# FlexLight.net
KiCad netlist of a schematic drawn in EasyEDA
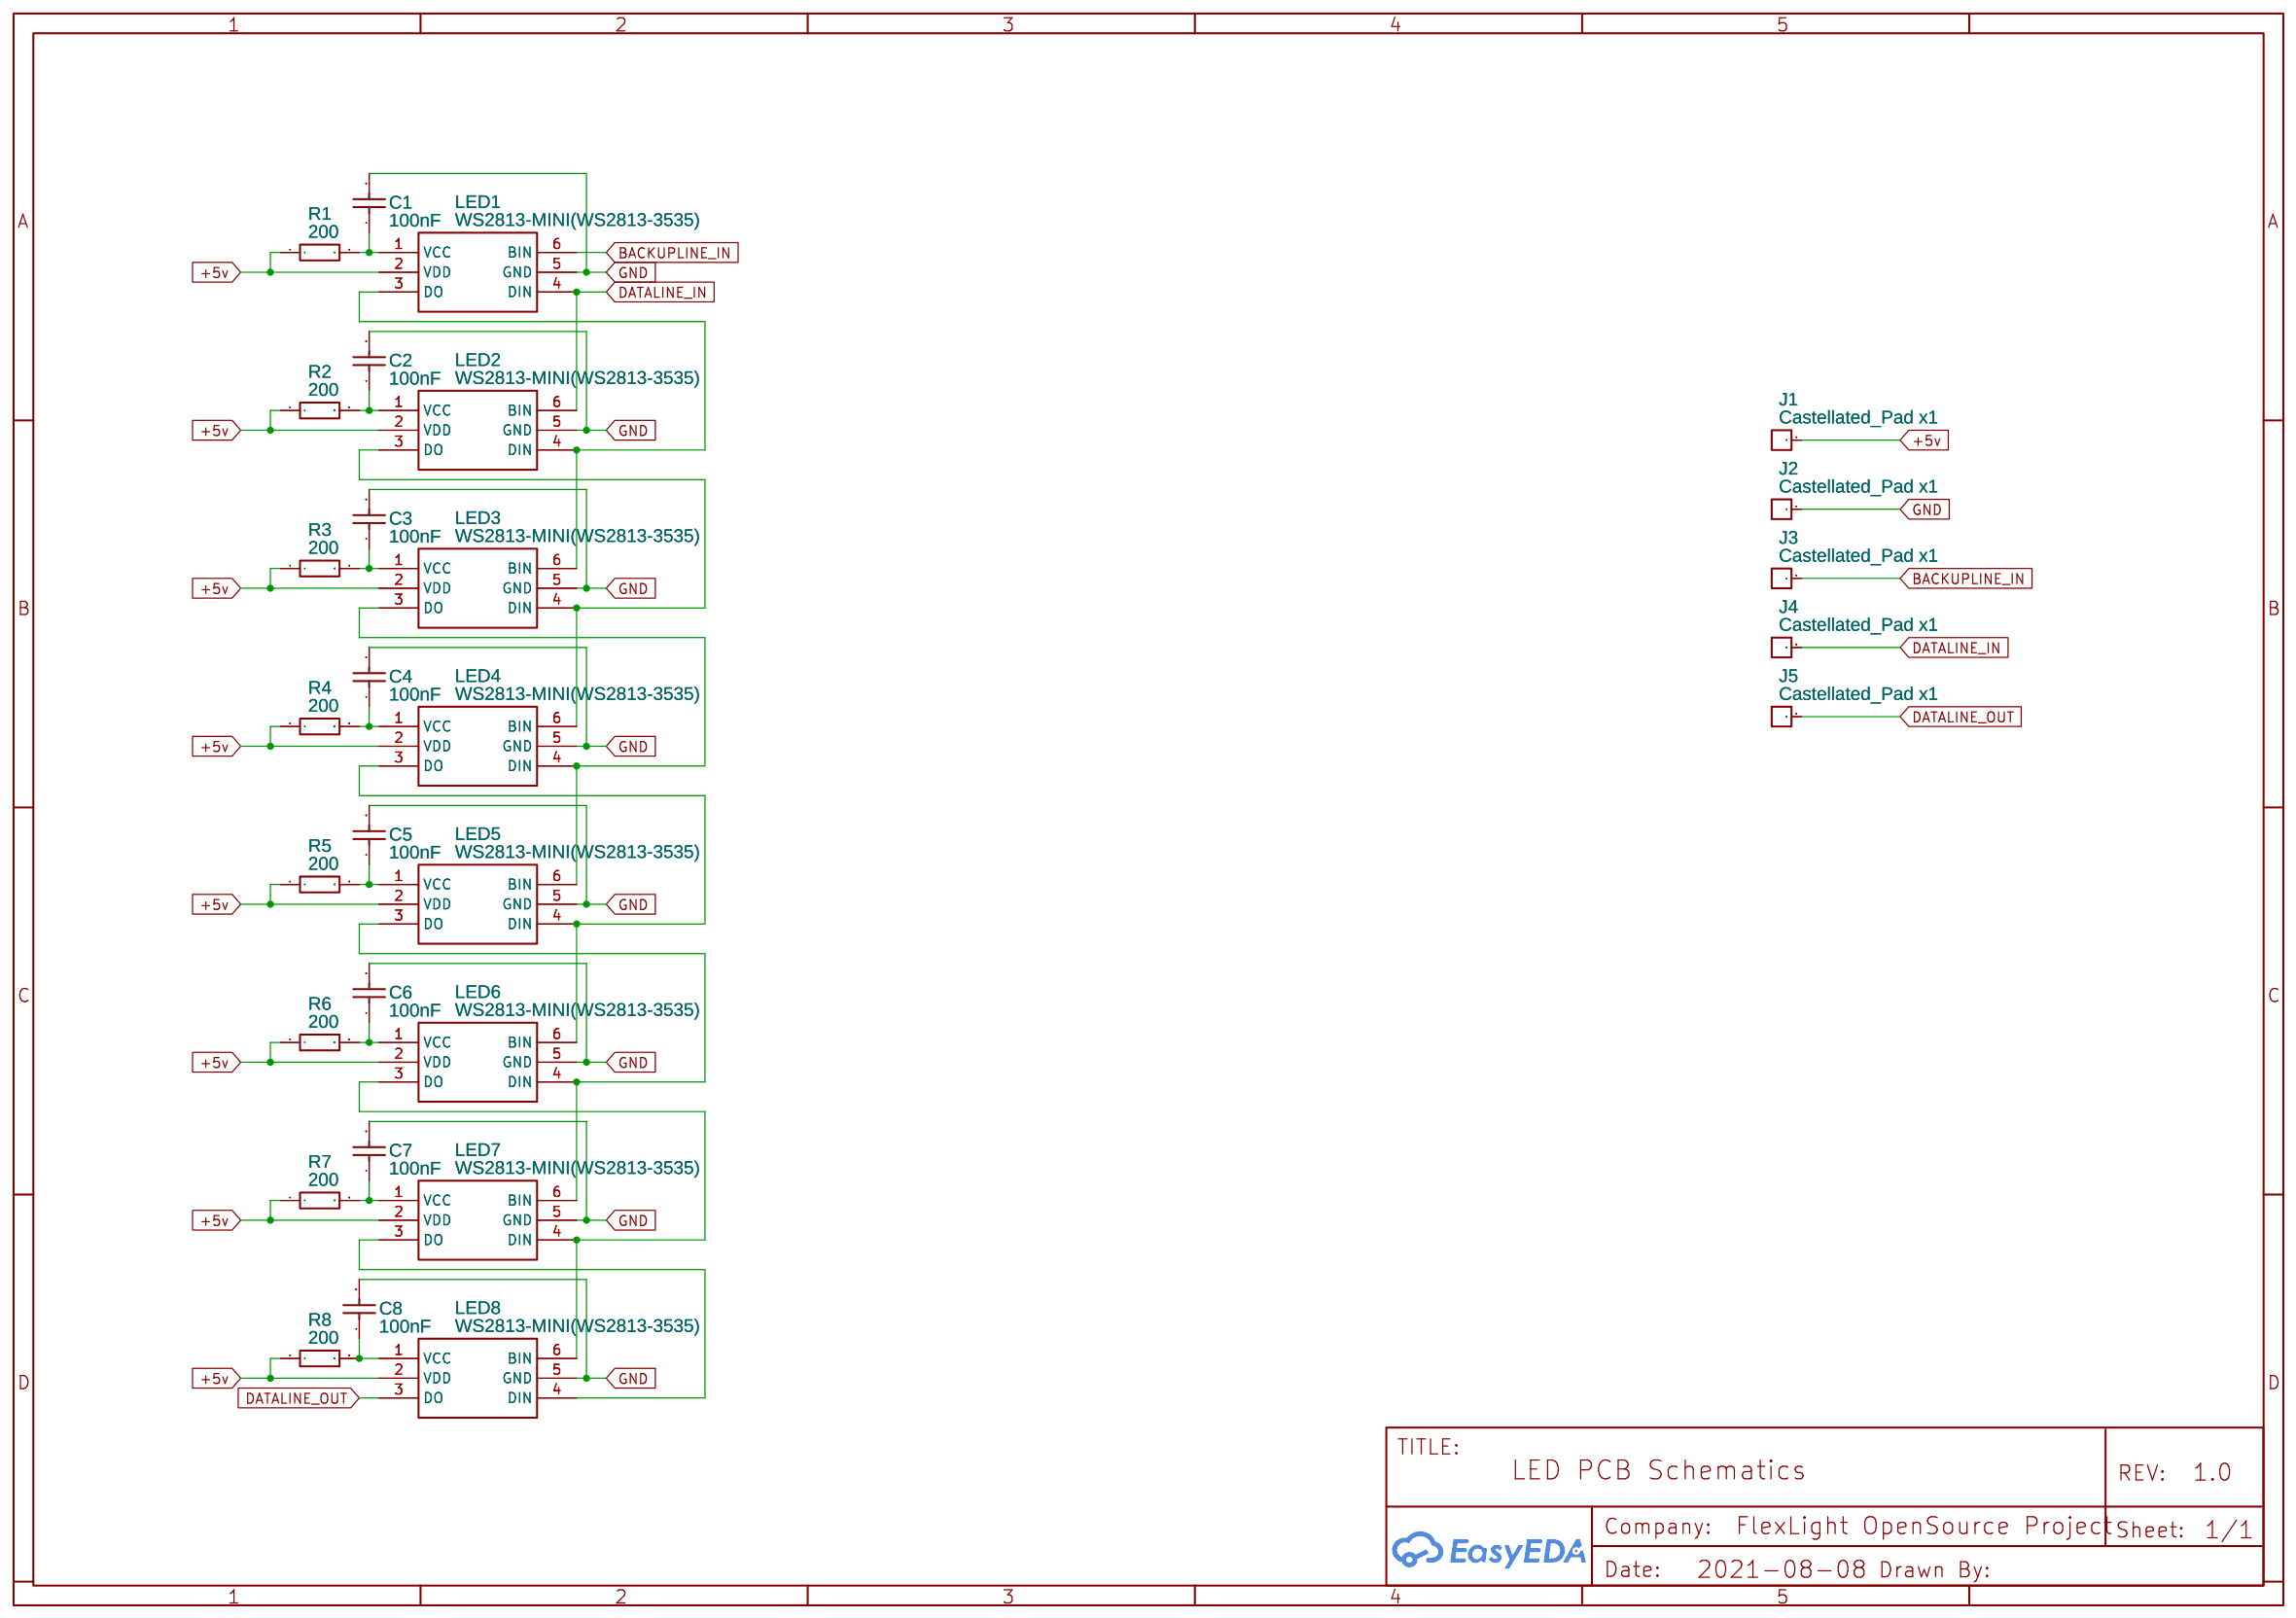
[diagram p0: schematic sheet]

(export (version "E")
  (design (tool "Eeschema 10.0.6"))
  (components
    (comp (ref "C1")
      (value "100nF")
      (fields
        (field (name "BOM_Manufacturer Part") "CL05B104KO5NNNC")
        (field (name "BOM_Supplier Part") "C1525")
      )
      (libsource (lib "") (part "CL05B104KO5NNNC"))
    )
    (comp (ref "C2")
      (value "100nF")
      (fields
        (field (name "BOM_Manufacturer Part") "CL05B104KO5NNNC")
        (field (name "BOM_Supplier Part") "C1525")
      )
      (libsource (lib "") (part "CL05B104KO5NNNC"))
    )
    (comp (ref "C3")
      (value "100nF")
      (fields
        (field (name "BOM_Manufacturer Part") "CL05B104KO5NNNC")
        (field (name "BOM_Supplier Part") "C1525")
      )
      (libsource (lib "") (part "CL05B104KO5NNNC"))
    )
    (comp (ref "C4")
      (value "100nF")
      (fields
        (field (name "BOM_Manufacturer Part") "CL05B104KO5NNNC")
        (field (name "BOM_Supplier Part") "C1525")
      )
      (libsource (lib "") (part "CL05B104KO5NNNC"))
    )
    (comp (ref "C5")
      (value "100nF")
      (fields
        (field (name "BOM_Manufacturer Part") "CL05B104KO5NNNC")
        (field (name "BOM_Supplier Part") "C1525")
      )
      (libsource (lib "") (part "CL05B104KO5NNNC"))
    )
    (comp (ref "C6")
      (value "100nF")
      (fields
        (field (name "BOM_Manufacturer Part") "CL05B104KO5NNNC")
        (field (name "BOM_Supplier Part") "C1525")
      )
      (libsource (lib "") (part "CL05B104KO5NNNC"))
    )
    (comp (ref "C7")
      (value "100nF")
      (fields
        (field (name "BOM_Manufacturer Part") "CL05B104KO5NNNC")
        (field (name "BOM_Supplier Part") "C1525")
      )
      (libsource (lib "") (part "CL05B104KO5NNNC"))
    )
    (comp (ref "C8")
      (value "100nF")
      (fields
        (field (name "BOM_Manufacturer Part") "CL05B104KO5NNNC")
        (field (name "BOM_Supplier Part") "C1525")
      )
      (libsource (lib "") (part "CL05B104KO5NNNC"))
    )
    (comp (ref "J1") (value "Castellated_Pad x1") (libsource (lib "") (part "Castellated_Pad x1")))
    (comp (ref "J2") (value "Castellated_Pad x1") (libsource (lib "") (part "Castellated_Pad x1")))
    (comp (ref "J3") (value "Castellated_Pad x1") (libsource (lib "") (part "Castellated_Pad x1")))
    (comp (ref "J4") (value "Castellated_Pad x1") (libsource (lib "") (part "Castellated_Pad x1")))
    (comp (ref "J5") (value "Castellated_Pad x1") (libsource (lib "") (part "Castellated_Pad x1")))
    (comp (ref "LED1")
      (value "WS2813-MINI(WS2813-3535)")
      (fields
        (field (name "BOM_Manufacturer Part") "WS2813-Mini(WS2813-3535)")
        (field (name "BOM_Supplier Part") "C189639")
      )
      (libsource (lib "") (part "WS2813-MINI(WS2813-3535)"))
    )
    (comp (ref "LED2")
      (value "WS2813-MINI(WS2813-3535)")
      (fields
        (field (name "BOM_Manufacturer Part") "WS2813-Mini(WS2813-3535)")
        (field (name "BOM_Supplier Part") "C189639")
      )
      (libsource (lib "") (part "WS2813-MINI(WS2813-3535)"))
    )
    (comp (ref "LED3")
      (value "WS2813-MINI(WS2813-3535)")
      (fields
        (field (name "BOM_Manufacturer Part") "WS2813-Mini(WS2813-3535)")
        (field (name "BOM_Supplier Part") "C189639")
      )
      (libsource (lib "") (part "WS2813-MINI(WS2813-3535)"))
    )
    (comp (ref "LED4")
      (value "WS2813-MINI(WS2813-3535)")
      (fields
        (field (name "BOM_Manufacturer Part") "WS2813-Mini(WS2813-3535)")
        (field (name "BOM_Supplier Part") "C189639")
      )
      (libsource (lib "") (part "WS2813-MINI(WS2813-3535)"))
    )
    (comp (ref "LED5")
      (value "WS2813-MINI(WS2813-3535)")
      (fields
        (field (name "BOM_Manufacturer Part") "WS2813-Mini(WS2813-3535)")
        (field (name "BOM_Supplier Part") "C189639")
      )
      (libsource (lib "") (part "WS2813-MINI(WS2813-3535)"))
    )
    (comp (ref "LED6")
      (value "WS2813-MINI(WS2813-3535)")
      (fields
        (field (name "BOM_Manufacturer Part") "WS2813-Mini(WS2813-3535)")
        (field (name "BOM_Supplier Part") "C189639")
      )
      (libsource (lib "") (part "WS2813-MINI(WS2813-3535)"))
    )
    (comp (ref "LED7")
      (value "WS2813-MINI(WS2813-3535)")
      (fields
        (field (name "BOM_Manufacturer Part") "WS2813-Mini(WS2813-3535)")
        (field (name "BOM_Supplier Part") "C189639")
      )
      (libsource (lib "") (part "WS2813-MINI(WS2813-3535)"))
    )
    (comp (ref "LED8")
      (value "WS2813-MINI(WS2813-3535)")
      (fields
        (field (name "BOM_Manufacturer Part") "WS2813-Mini(WS2813-3535)")
        (field (name "BOM_Supplier Part") "C189639")
      )
      (libsource (lib "") (part "WS2813-MINI(WS2813-3535)"))
    )
    (comp (ref "R1")
      (value "200")
      (fields
        (field (name "BOM_Manufacturer Part") "0402WGF2000TCE")
        (field (name "BOM_Supplier Part") "C25087")
      )
      (libsource (lib "") (part "0402WGF2000TCE"))
    )
    (comp (ref "R2")
      (value "200")
      (fields
        (field (name "BOM_Manufacturer Part") "0402WGF2000TCE")
        (field (name "BOM_Supplier Part") "C25087")
      )
      (libsource (lib "") (part "0402WGF2000TCE"))
    )
    (comp (ref "R3")
      (value "200")
      (fields
        (field (name "BOM_Manufacturer Part") "0402WGF2000TCE")
        (field (name "BOM_Supplier Part") "C25087")
      )
      (libsource (lib "") (part "0402WGF2000TCE"))
    )
    (comp (ref "R4")
      (value "200")
      (fields
        (field (name "BOM_Manufacturer Part") "0402WGF2000TCE")
        (field (name "BOM_Supplier Part") "C25087")
      )
      (libsource (lib "") (part "0402WGF2000TCE"))
    )
    (comp (ref "R5")
      (value "200")
      (fields
        (field (name "BOM_Manufacturer Part") "0402WGF2000TCE")
        (field (name "BOM_Supplier Part") "C25087")
      )
      (libsource (lib "") (part "0402WGF2000TCE"))
    )
    (comp (ref "R6")
      (value "200")
      (fields
        (field (name "BOM_Manufacturer Part") "0402WGF2000TCE")
        (field (name "BOM_Supplier Part") "C25087")
      )
      (libsource (lib "") (part "0402WGF2000TCE"))
    )
    (comp (ref "R7")
      (value "200")
      (fields
        (field (name "BOM_Manufacturer Part") "0402WGF2000TCE")
        (field (name "BOM_Supplier Part") "C25087")
      )
      (libsource (lib "") (part "0402WGF2000TCE"))
    )
    (comp (ref "R8")
      (value "200")
      (fields
        (field (name "BOM_Manufacturer Part") "0402WGF2000TCE")
        (field (name "BOM_Supplier Part") "C25087")
      )
      (libsource (lib "") (part "0402WGF2000TCE"))
    )
  )
  (nets
    (net (code "1") (name "+5v") (class "Default")
      (node (ref "J1") (pin "1") (pinfunction "P_1") (pintype "unspecified"))
      (node (ref "LED1") (pin "2") (pinfunction "VDD_2") (pintype "unspecified"))
      (node (ref "LED2") (pin "2") (pinfunction "VDD_2") (pintype "unspecified"))
      (node (ref "LED3") (pin "2") (pinfunction "VDD_2") (pintype "unspecified"))
      (node (ref "LED4") (pin "2") (pinfunction "VDD_2") (pintype "unspecified"))
      (node (ref "LED5") (pin "2") (pinfunction "VDD_2") (pintype "unspecified"))
      (node (ref "LED6") (pin "2") (pinfunction "VDD_2") (pintype "unspecified"))
      (node (ref "LED7") (pin "2") (pinfunction "VDD_2") (pintype "unspecified"))
      (node (ref "LED8") (pin "2") (pinfunction "VDD_2") (pintype "unspecified"))
      (node (ref "R1") (pin "1") (pinfunction "1_1") (pintype "input"))
      (node (ref "R2") (pin "1") (pinfunction "1_1") (pintype "input"))
      (node (ref "R3") (pin "1") (pinfunction "1_1") (pintype "input"))
      (node (ref "R4") (pin "1") (pinfunction "1_1") (pintype "input"))
      (node (ref "R5") (pin "1") (pinfunction "1_1") (pintype "input"))
      (node (ref "R6") (pin "1") (pinfunction "1_1") (pintype "input"))
      (node (ref "R7") (pin "1") (pinfunction "1_1") (pintype "input"))
      (node (ref "R8") (pin "1") (pinfunction "1_1") (pintype "input"))
    )
    (net (code "2") (name "BACKUPLINE_IN") (class "Default")
      (node (ref "J3") (pin "1") (pinfunction "P_1") (pintype "unspecified"))
      (node (ref "LED1") (pin "6") (pinfunction "BIN_6") (pintype "unspecified"))
    )
    (net (code "3") (name "DATALINE_IN") (class "Default")
      (node (ref "J4") (pin "1") (pinfunction "P_1") (pintype "unspecified"))
      (node (ref "LED1") (pin "4") (pinfunction "DIN_4") (pintype "unspecified"))
      (node (ref "LED2") (pin "6") (pinfunction "BIN_6") (pintype "unspecified"))
    )
    (net (code "4") (name "DATALINE_OUT") (class "Default")
      (node (ref "J5") (pin "1") (pinfunction "P_1") (pintype "unspecified"))
      (node (ref "LED8") (pin "3") (pinfunction "DO_3") (pintype "unspecified"))
    )
    (net (code "5") (name "GND") (class "Default")
      (node (ref "C1") (pin "2") (pinfunction "2_2") (pintype "input"))
      (node (ref "C2") (pin "2") (pinfunction "2_2") (pintype "input"))
      (node (ref "C3") (pin "2") (pinfunction "2_2") (pintype "input"))
      (node (ref "C4") (pin "2") (pinfunction "2_2") (pintype "input"))
      (node (ref "C5") (pin "2") (pinfunction "2_2") (pintype "input"))
      (node (ref "C6") (pin "2") (pinfunction "2_2") (pintype "input"))
      (node (ref "C7") (pin "2") (pinfunction "2_2") (pintype "input"))
      (node (ref "C8") (pin "2") (pinfunction "2_2") (pintype "input"))
      (node (ref "J2") (pin "1") (pinfunction "P_1") (pintype "unspecified"))
      (node (ref "LED1") (pin "5") (pinfunction "GND_5") (pintype "unspecified"))
      (node (ref "LED2") (pin "5") (pinfunction "GND_5") (pintype "unspecified"))
      (node (ref "LED3") (pin "5") (pinfunction "GND_5") (pintype "unspecified"))
      (node (ref "LED4") (pin "5") (pinfunction "GND_5") (pintype "unspecified"))
      (node (ref "LED5") (pin "5") (pinfunction "GND_5") (pintype "unspecified"))
      (node (ref "LED6") (pin "5") (pinfunction "GND_5") (pintype "unspecified"))
      (node (ref "LED7") (pin "5") (pinfunction "GND_5") (pintype "unspecified"))
      (node (ref "LED8") (pin "5") (pinfunction "GND_5") (pintype "unspecified"))
    )
    (net (code "6") (name "Net-(LED1-DO)") (class "Default")
      (node (ref "LED1") (pin "3") (pinfunction "DO_3") (pintype "unspecified"))
      (node (ref "LED2") (pin "4") (pinfunction "DIN_4") (pintype "unspecified"))
      (node (ref "LED3") (pin "6") (pinfunction "BIN_6") (pintype "unspecified"))
    )
    (net (code "7") (name "Net-(LED1-VCC)") (class "Default")
      (node (ref "C1") (pin "1") (pinfunction "1_1") (pintype "input"))
      (node (ref "LED1") (pin "1") (pinfunction "VCC_1") (pintype "unspecified"))
      (node (ref "R1") (pin "2") (pinfunction "2_2") (pintype "input"))
    )
    (net (code "8") (name "Net-(LED2-DO)") (class "Default")
      (node (ref "LED2") (pin "3") (pinfunction "DO_3") (pintype "unspecified"))
      (node (ref "LED3") (pin "4") (pinfunction "DIN_4") (pintype "unspecified"))
      (node (ref "LED4") (pin "6") (pinfunction "BIN_6") (pintype "unspecified"))
    )
    (net (code "9") (name "Net-(LED2-VCC)") (class "Default")
      (node (ref "C2") (pin "1") (pinfunction "1_1") (pintype "input"))
      (node (ref "LED2") (pin "1") (pinfunction "VCC_1") (pintype "unspecified"))
      (node (ref "R2") (pin "2") (pinfunction "2_2") (pintype "input"))
    )
    (net (code "10") (name "Net-(LED3-DO)") (class "Default")
      (node (ref "LED3") (pin "3") (pinfunction "DO_3") (pintype "unspecified"))
      (node (ref "LED4") (pin "4") (pinfunction "DIN_4") (pintype "unspecified"))
      (node (ref "LED5") (pin "6") (pinfunction "BIN_6") (pintype "unspecified"))
    )
    (net (code "11") (name "Net-(LED3-VCC)") (class "Default")
      (node (ref "C3") (pin "1") (pinfunction "1_1") (pintype "input"))
      (node (ref "LED3") (pin "1") (pinfunction "VCC_1") (pintype "unspecified"))
      (node (ref "R3") (pin "2") (pinfunction "2_2") (pintype "input"))
    )
    (net (code "12") (name "Net-(LED4-DO)") (class "Default")
      (node (ref "LED4") (pin "3") (pinfunction "DO_3") (pintype "unspecified"))
      (node (ref "LED5") (pin "4") (pinfunction "DIN_4") (pintype "unspecified"))
      (node (ref "LED6") (pin "6") (pinfunction "BIN_6") (pintype "unspecified"))
    )
    (net (code "13") (name "Net-(LED4-VCC)") (class "Default")
      (node (ref "C4") (pin "1") (pinfunction "1_1") (pintype "input"))
      (node (ref "LED4") (pin "1") (pinfunction "VCC_1") (pintype "unspecified"))
      (node (ref "R4") (pin "2") (pinfunction "2_2") (pintype "input"))
    )
    (net (code "14") (name "Net-(LED5-DO)") (class "Default")
      (node (ref "LED5") (pin "3") (pinfunction "DO_3") (pintype "unspecified"))
      (node (ref "LED6") (pin "4") (pinfunction "DIN_4") (pintype "unspecified"))
      (node (ref "LED7") (pin "6") (pinfunction "BIN_6") (pintype "unspecified"))
    )
    (net (code "15") (name "Net-(LED5-VCC)") (class "Default")
      (node (ref "C5") (pin "1") (pinfunction "1_1") (pintype "input"))
      (node (ref "LED5") (pin "1") (pinfunction "VCC_1") (pintype "unspecified"))
      (node (ref "R5") (pin "2") (pinfunction "2_2") (pintype "input"))
    )
    (net (code "16") (name "Net-(LED6-DO)") (class "Default")
      (node (ref "LED6") (pin "3") (pinfunction "DO_3") (pintype "unspecified"))
      (node (ref "LED7") (pin "4") (pinfunction "DIN_4") (pintype "unspecified"))
      (node (ref "LED8") (pin "6") (pinfunction "BIN_6") (pintype "unspecified"))
    )
    (net (code "17") (name "Net-(LED6-VCC)") (class "Default")
      (node (ref "C6") (pin "1") (pinfunction "1_1") (pintype "input"))
      (node (ref "LED6") (pin "1") (pinfunction "VCC_1") (pintype "unspecified"))
      (node (ref "R6") (pin "2") (pinfunction "2_2") (pintype "input"))
    )
    (net (code "18") (name "Net-(LED7-DO)") (class "Default")
      (node (ref "LED7") (pin "3") (pinfunction "DO_3") (pintype "unspecified"))
      (node (ref "LED8") (pin "4") (pinfunction "DIN_4") (pintype "unspecified"))
    )
    (net (code "19") (name "Net-(LED7-VCC)") (class "Default")
      (node (ref "C7") (pin "1") (pinfunction "1_1") (pintype "input"))
      (node (ref "LED7") (pin "1") (pinfunction "VCC_1") (pintype "unspecified"))
      (node (ref "R7") (pin "2") (pinfunction "2_2") (pintype "input"))
    )
    (net (code "20") (name "Net-(LED8-VCC)") (class "Default")
      (node (ref "C8") (pin "1") (pinfunction "1_1") (pintype "input"))
      (node (ref "LED8") (pin "1") (pinfunction "VCC_1") (pintype "unspecified"))
      (node (ref "R8") (pin "2") (pinfunction "2_2") (pintype "input"))
    )
  )
)
